# latch7.net
KiCad netlist of a schematic drawn in EAGLE
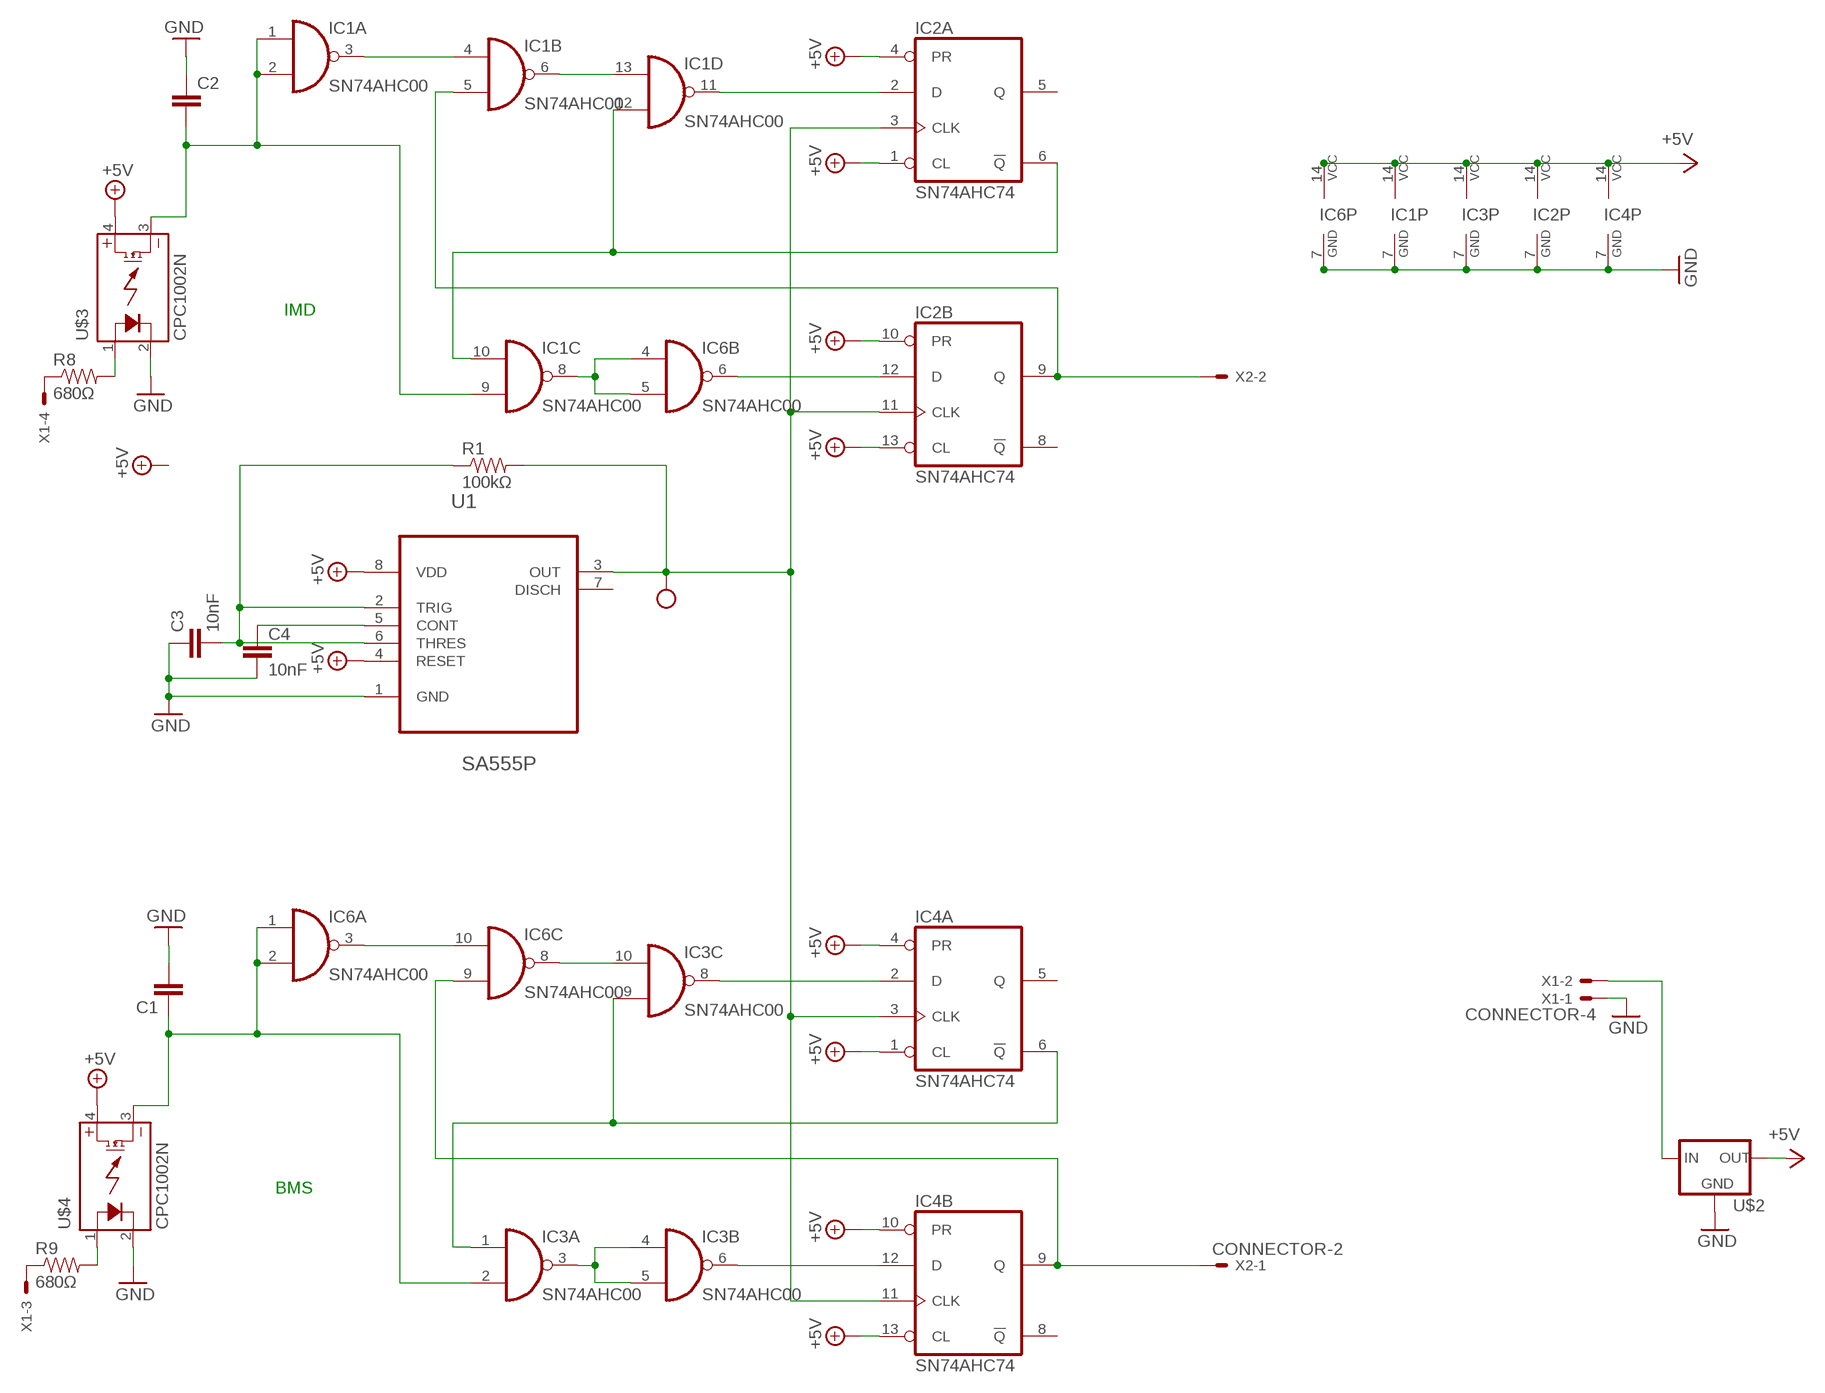
[diagram p0: schematic, sheet 1]

(export (version "E")
  (design (tool "Eeschema 10.0.6"))
  (components
    (comp (ref "C1")
      (value "CAP_")
      (footprint "eagle-import:AXIAL-5MM")
      (libsource (lib "eagle-import") (part "CAP_"))
    )
    (comp (ref "C2")
      (value "CAP_")
      (footprint "eagle-import:AXIAL-5MM")
      (libsource (lib "eagle-import") (part "CAP_"))
    )
    (comp (ref "C3")
      (value "10nF")
      (footprint "eagle-import:AXIAL-5MM")
      (libsource (lib "eagle-import") (part "CAP_"))
    )
    (comp (ref "C4")
      (value "10nF")
      (footprint "eagle-import:AXIAL-5MM")
      (libsource (lib "eagle-import") (part "CAP_"))
    )
    (comp (ref "IC1")
      (value "SN74AHC00")
      (footprint "eagle-import:DIL14")
      (libsource (lib "eagle-import") (part "SN74AHC00"))
    )
    (comp (ref "IC2")
      (value "SN74AHC74")
      (footprint "eagle-import:DIL14")
      (libsource (lib "eagle-import") (part "SN74AHC74"))
    )
    (comp (ref "IC3")
      (value "SN74AHC00")
      (footprint "eagle-import:DIL14")
      (libsource (lib "eagle-import") (part "SN74AHC00"))
    )
    (comp (ref "IC4")
      (value "SN74AHC74")
      (footprint "eagle-import:DIL14")
      (libsource (lib "eagle-import") (part "SN74AHC74"))
    )
    (comp (ref "IC6")
      (value "SN74AHC00")
      (footprint "eagle-import:DIL14")
      (libsource (lib "eagle-import") (part "SN74AHC00"))
    )
    (comp (ref "R1")
      (value "100kΩ")
      (footprint "eagle-import:AXIAL-0.4")
      (libsource (lib "eagle-import") (part "RESISTORPTH-1/4W"))
    )
    (comp (ref "R8")
      (value "680Ω")
      (footprint "eagle-import:AXIAL-0.4")
      (libsource (lib "eagle-import") (part "RESISTORPTH-1/4W"))
    )
    (comp (ref "R9")
      (value "680Ω")
      (footprint "eagle-import:AXIAL-0.4")
      (libsource (lib "eagle-import") (part "RESISTORPTH-1/4W"))
    )
    (comp (ref "U$1")
      (value "TEST_POINT")
      (footprint "eagle-import:TEST_POINT")
      (libsource (lib "eagle-import") (part "TEST_POINT"))
    )
    (comp (ref "U$2")
      (value "5VREG_LM340-NLM340T-5.0/NOPB")
      (footprint "eagle-import:TO-220")
      (libsource (lib "eagle-import") (part "5VREG_LM340-NLM340T-5.0/NOPB"))
    )
    (comp (ref "U$3")
      (value "CPC1002N")
      (footprint "eagle-import:SOP04")
      (libsource (lib "eagle-import") (part "CPC1002N"))
    )
    (comp (ref "U$4")
      (value "CPC1002N")
      (footprint "eagle-import:SOP04")
      (libsource (lib "eagle-import") (part "CPC1002N"))
    )
    (comp (ref "U1")
      (value "SA555P")
      (footprint "eagle-import:DIP254P762X508-8")
      (libsource (lib "eagle-import") (part "SA555P"))
    )
    (comp (ref "X1")
      (value "CONNECTOR-4")
      (footprint "eagle-import:MINIFIT_5566-4")
      (libsource (lib "eagle-import") (part "CONNECTOR-4"))
    )
    (comp (ref "X2")
      (value "CONNECTOR-2")
      (footprint "eagle-import:MINIFIT_5566-2")
      (libsource (lib "eagle-import") (part "CONNECTOR-2"))
    )
  )
  (nets
    (net (code "1") (name "+5V") (class "Default")
      (node (ref "IC1") (pin "14") (pinfunction "VCC_14") (pintype "power_in"))
      (node (ref "IC2") (pin "1") (pinfunction "CL_1") (pintype "input"))
      (node (ref "IC2") (pin "10") (pinfunction "PR_10") (pintype "input"))
      (node (ref "IC2") (pin "13") (pinfunction "CL_13") (pintype "input"))
      (node (ref "IC2") (pin "14") (pinfunction "VCC_14") (pintype "power_in"))
      (node (ref "IC2") (pin "4") (pinfunction "PR_4") (pintype "input"))
      (node (ref "IC3") (pin "14") (pinfunction "VCC_14") (pintype "power_in"))
      (node (ref "IC4") (pin "1") (pinfunction "CL_1") (pintype "input"))
      (node (ref "IC4") (pin "10") (pinfunction "PR_10") (pintype "input"))
      (node (ref "IC4") (pin "13") (pinfunction "CL_13") (pintype "input"))
      (node (ref "IC4") (pin "14") (pinfunction "VCC_14") (pintype "power_in"))
      (node (ref "IC4") (pin "4") (pinfunction "PR_4") (pintype "input"))
      (node (ref "IC6") (pin "14") (pinfunction "VCC_14") (pintype "power_in"))
      (node (ref "U$2") (pin "3") (pinfunction "OUT_3") (pintype "output"))
      (node (ref "U$3") (pin "4") (pinfunction "DC+_4") (pintype "passive"))
      (node (ref "U$4") (pin "4") (pinfunction "DC+_4") (pintype "passive"))
      (node (ref "U1") (pin "4") (pinfunction "RESET_4") (pintype "input"))
      (node (ref "U1") (pin "8") (pinfunction "VDD_8") (pintype "power_in"))
    )
    (net (code "2") (name "GND") (class "Default")
      (node (ref "C1") (pin "P$2") (pinfunction "2_P$2") (pintype "passive"))
      (node (ref "C2") (pin "P$1") (pinfunction "1_P$1") (pintype "passive"))
      (node (ref "C3") (pin "P$1") (pinfunction "1_P$1") (pintype "passive"))
      (node (ref "C4") (pin "P$2") (pinfunction "2_P$2") (pintype "passive"))
      (node (ref "IC1") (pin "7") (pinfunction "GND_7") (pintype "power_in"))
      (node (ref "IC2") (pin "7") (pinfunction "GND_7") (pintype "power_in"))
      (node (ref "IC3") (pin "7") (pinfunction "GND_7") (pintype "power_in"))
      (node (ref "IC4") (pin "7") (pinfunction "GND_7") (pintype "power_in"))
      (node (ref "IC6") (pin "7") (pinfunction "GND_7") (pintype "power_in"))
      (node (ref "U$2") (pin "2") (pinfunction "GND_2") (pintype "input"))
      (node (ref "U$3") (pin "2") (pinfunction "CONTROL-_2") (pintype "passive"))
      (node (ref "U$4") (pin "2") (pinfunction "CONTROL-_2") (pintype "passive"))
      (node (ref "U1") (pin "1") (pinfunction "GND_1") (pintype "passive"))
      (node (ref "X1") (pin "1") (pinfunction "S_1") (pintype "passive"))
    )
    (net (code "3") (name "Net-(C1-1)") (class "Default")
      (node (ref "C1") (pin "P$1") (pinfunction "1_P$1") (pintype "passive"))
      (node (ref "IC3") (pin "2") (pinfunction "I1_2") (pintype "input"))
      (node (ref "IC6") (pin "1") (pinfunction "I0_1") (pintype "input"))
      (node (ref "IC6") (pin "2") (pinfunction "I1_2") (pintype "input"))
      (node (ref "U$4") (pin "3") (pinfunction "DC-_3") (pintype "passive"))
    )
    (net (code "4") (name "Net-(C2-2)") (class "Default")
      (node (ref "C2") (pin "P$2") (pinfunction "2_P$2") (pintype "passive"))
      (node (ref "IC1") (pin "1") (pinfunction "I0_1") (pintype "input"))
      (node (ref "IC1") (pin "2") (pinfunction "I1_2") (pintype "input"))
      (node (ref "IC1") (pin "9") (pinfunction "I1_9") (pintype "input"))
      (node (ref "U$3") (pin "3") (pinfunction "DC-_3") (pintype "passive"))
    )
    (net (code "5") (name "Net-(C3-2)") (class "Default")
      (node (ref "C3") (pin "P$2") (pinfunction "2_P$2") (pintype "passive"))
      (node (ref "R1") (pin "P$1") (pinfunction "1_P$1") (pintype "passive"))
      (node (ref "U1") (pin "2") (pinfunction "TRIG_2") (pintype "input"))
      (node (ref "U1") (pin "6") (pinfunction "THRES_6") (pintype "input"))
    )
    (net (code "6") (name "Net-(C4-1)") (class "Default")
      (node (ref "C4") (pin "P$1") (pinfunction "1_P$1") (pintype "passive"))
      (node (ref "U1") (pin "5") (pinfunction "CONT_5") (pintype "input"))
    )
    (net (code "7") (name "Net-(IC1A-O)") (class "Default")
      (node (ref "IC1") (pin "3") (pinfunction "O_3") (pintype "output"))
      (node (ref "IC1") (pin "4") (pinfunction "I0_4") (pintype "input"))
    )
    (net (code "8") (name "Net-(IC1B-I1)") (class "Default")
      (node (ref "IC1") (pin "5") (pinfunction "I1_5") (pintype "input"))
      (node (ref "IC2") (pin "9") (pinfunction "Q_9") (pintype "output"))
      (node (ref "X2") (pin "2") (pinfunction "S_2") (pintype "passive"))
    )
    (net (code "9") (name "Net-(IC1B-O)") (class "Default")
      (node (ref "IC1") (pin "13") (pinfunction "I0_13") (pintype "input"))
      (node (ref "IC1") (pin "6") (pinfunction "O_6") (pintype "output"))
    )
    (net (code "10") (name "Net-(IC1C-I0)") (class "Default")
      (node (ref "IC1") (pin "10") (pinfunction "I0_10") (pintype "input"))
      (node (ref "IC1") (pin "12") (pinfunction "I1_12") (pintype "input"))
      (node (ref "IC2") (pin "6") (pinfunction "~{Q}_6") (pintype "output"))
    )
    (net (code "11") (name "Net-(IC1C-O)") (class "Default")
      (node (ref "IC1") (pin "8") (pinfunction "O_8") (pintype "output"))
      (node (ref "IC6") (pin "4") (pinfunction "I0_4") (pintype "input"))
      (node (ref "IC6") (pin "5") (pinfunction "I1_5") (pintype "input"))
    )
    (net (code "12") (name "Net-(IC1D-O)") (class "Default")
      (node (ref "IC1") (pin "11") (pinfunction "O_11") (pintype "output"))
      (node (ref "IC2") (pin "2") (pinfunction "D_2") (pintype "input"))
    )
    (net (code "13") (name "Net-(IC2A-CLK)") (class "Default")
      (node (ref "IC2") (pin "11") (pinfunction "CLK_11") (pintype "input"))
      (node (ref "IC2") (pin "3") (pinfunction "CLK_3") (pintype "input"))
      (node (ref "IC4") (pin "11") (pinfunction "CLK_11") (pintype "input"))
      (node (ref "IC4") (pin "3") (pinfunction "CLK_3") (pintype "input"))
      (node (ref "R1") (pin "P$2") (pinfunction "2_P$2") (pintype "passive"))
      (node (ref "U$1") (pin "P$1") (pinfunction "P$1_P$1") (pintype "bidirectional"))
      (node (ref "U1") (pin "3") (pinfunction "OUT_3") (pintype "output"))
    )
    (net (code "14") (name "Net-(IC2B-D)") (class "Default")
      (node (ref "IC2") (pin "12") (pinfunction "D_12") (pintype "input"))
      (node (ref "IC6") (pin "6") (pinfunction "O_6") (pintype "output"))
    )
    (net (code "15") (name "Net-(IC3A-I0)") (class "Default")
      (node (ref "IC3") (pin "1") (pinfunction "I0_1") (pintype "input"))
      (node (ref "IC3") (pin "9") (pinfunction "I1_9") (pintype "input"))
      (node (ref "IC4") (pin "6") (pinfunction "~{Q}_6") (pintype "output"))
    )
    (net (code "16") (name "Net-(IC3A-O)") (class "Default")
      (node (ref "IC3") (pin "3") (pinfunction "O_3") (pintype "output"))
      (node (ref "IC3") (pin "4") (pinfunction "I0_4") (pintype "input"))
      (node (ref "IC3") (pin "5") (pinfunction "I1_5") (pintype "input"))
    )
    (net (code "17") (name "Net-(IC3B-O)") (class "Default")
      (node (ref "IC3") (pin "6") (pinfunction "O_6") (pintype "output"))
      (node (ref "IC4") (pin "12") (pinfunction "D_12") (pintype "input"))
    )
    (net (code "18") (name "Net-(IC3C-I0)") (class "Default")
      (node (ref "IC3") (pin "10") (pinfunction "I0_10") (pintype "input"))
      (node (ref "IC6") (pin "8") (pinfunction "O_8") (pintype "output"))
    )
    (net (code "19") (name "Net-(IC3C-O)") (class "Default")
      (node (ref "IC3") (pin "8") (pinfunction "O_8") (pintype "output"))
      (node (ref "IC4") (pin "2") (pinfunction "D_2") (pintype "input"))
    )
    (net (code "20") (name "Net-(IC4B-Q)") (class "Default")
      (node (ref "IC4") (pin "9") (pinfunction "Q_9") (pintype "output"))
      (node (ref "IC6") (pin "9") (pinfunction "I1_9") (pintype "input"))
      (node (ref "X2") (pin "1") (pinfunction "S_1") (pintype "passive"))
    )
    (net (code "21") (name "Net-(IC6A-O)") (class "Default")
      (node (ref "IC6") (pin "10") (pinfunction "I0_10") (pintype "input"))
      (node (ref "IC6") (pin "3") (pinfunction "O_3") (pintype "output"))
    )
    (net (code "22") (name "Net-(R8-1)") (class "Default")
      (node (ref "R8") (pin "P$1") (pinfunction "1_P$1") (pintype "passive"))
      (node (ref "X1") (pin "4") (pinfunction "S_4") (pintype "passive"))
    )
    (net (code "23") (name "Net-(R8-2)") (class "Default")
      (node (ref "R8") (pin "P$2") (pinfunction "2_P$2") (pintype "passive"))
      (node (ref "U$3") (pin "1") (pinfunction "CONTROL+_1") (pintype "passive"))
    )
    (net (code "24") (name "Net-(R9-1)") (class "Default")
      (node (ref "R9") (pin "P$1") (pinfunction "1_P$1") (pintype "passive"))
      (node (ref "X1") (pin "3") (pinfunction "S_3") (pintype "passive"))
    )
    (net (code "25") (name "Net-(R9-2)") (class "Default")
      (node (ref "R9") (pin "P$2") (pinfunction "2_P$2") (pintype "passive"))
      (node (ref "U$4") (pin "1") (pinfunction "CONTROL+_1") (pintype "passive"))
    )
    (net (code "26") (name "Net-(U$2-IN)") (class "Default")
      (node (ref "U$2") (pin "1") (pinfunction "IN_1") (pintype "input"))
      (node (ref "X1") (pin "2") (pinfunction "S_2") (pintype "passive"))
    )
    (net (code "27") (name "unconnected-(IC2A-Q-Pad5)") (class "Default")
      (node (ref "IC2") (pin "5") (pinfunction "Q_5") (pintype "output"))
    )
    (net (code "28") (name "unconnected-(IC2B-~{Q}-Pad8)") (class "Default")
      (node (ref "IC2") (pin "8") (pinfunction "~{Q}_8") (pintype "output"))
    )
    (net (code "29") (name "unconnected-(IC4A-Q-Pad5)") (class "Default")
      (node (ref "IC4") (pin "5") (pinfunction "Q_5") (pintype "output"))
    )
    (net (code "30") (name "unconnected-(IC4B-~{Q}-Pad8)") (class "Default")
      (node (ref "IC4") (pin "8") (pinfunction "~{Q}_8") (pintype "output"))
    )
    (net (code "31") (name "unconnected-(U1-DISCH-Pad7)") (class "Default")
      (node (ref "U1") (pin "7") (pinfunction "DISCH_7") (pintype "output"))
    )
  )
)
